# Triangle_VCO.net
KiCad netlist of a schematic drawn in Altium Designer
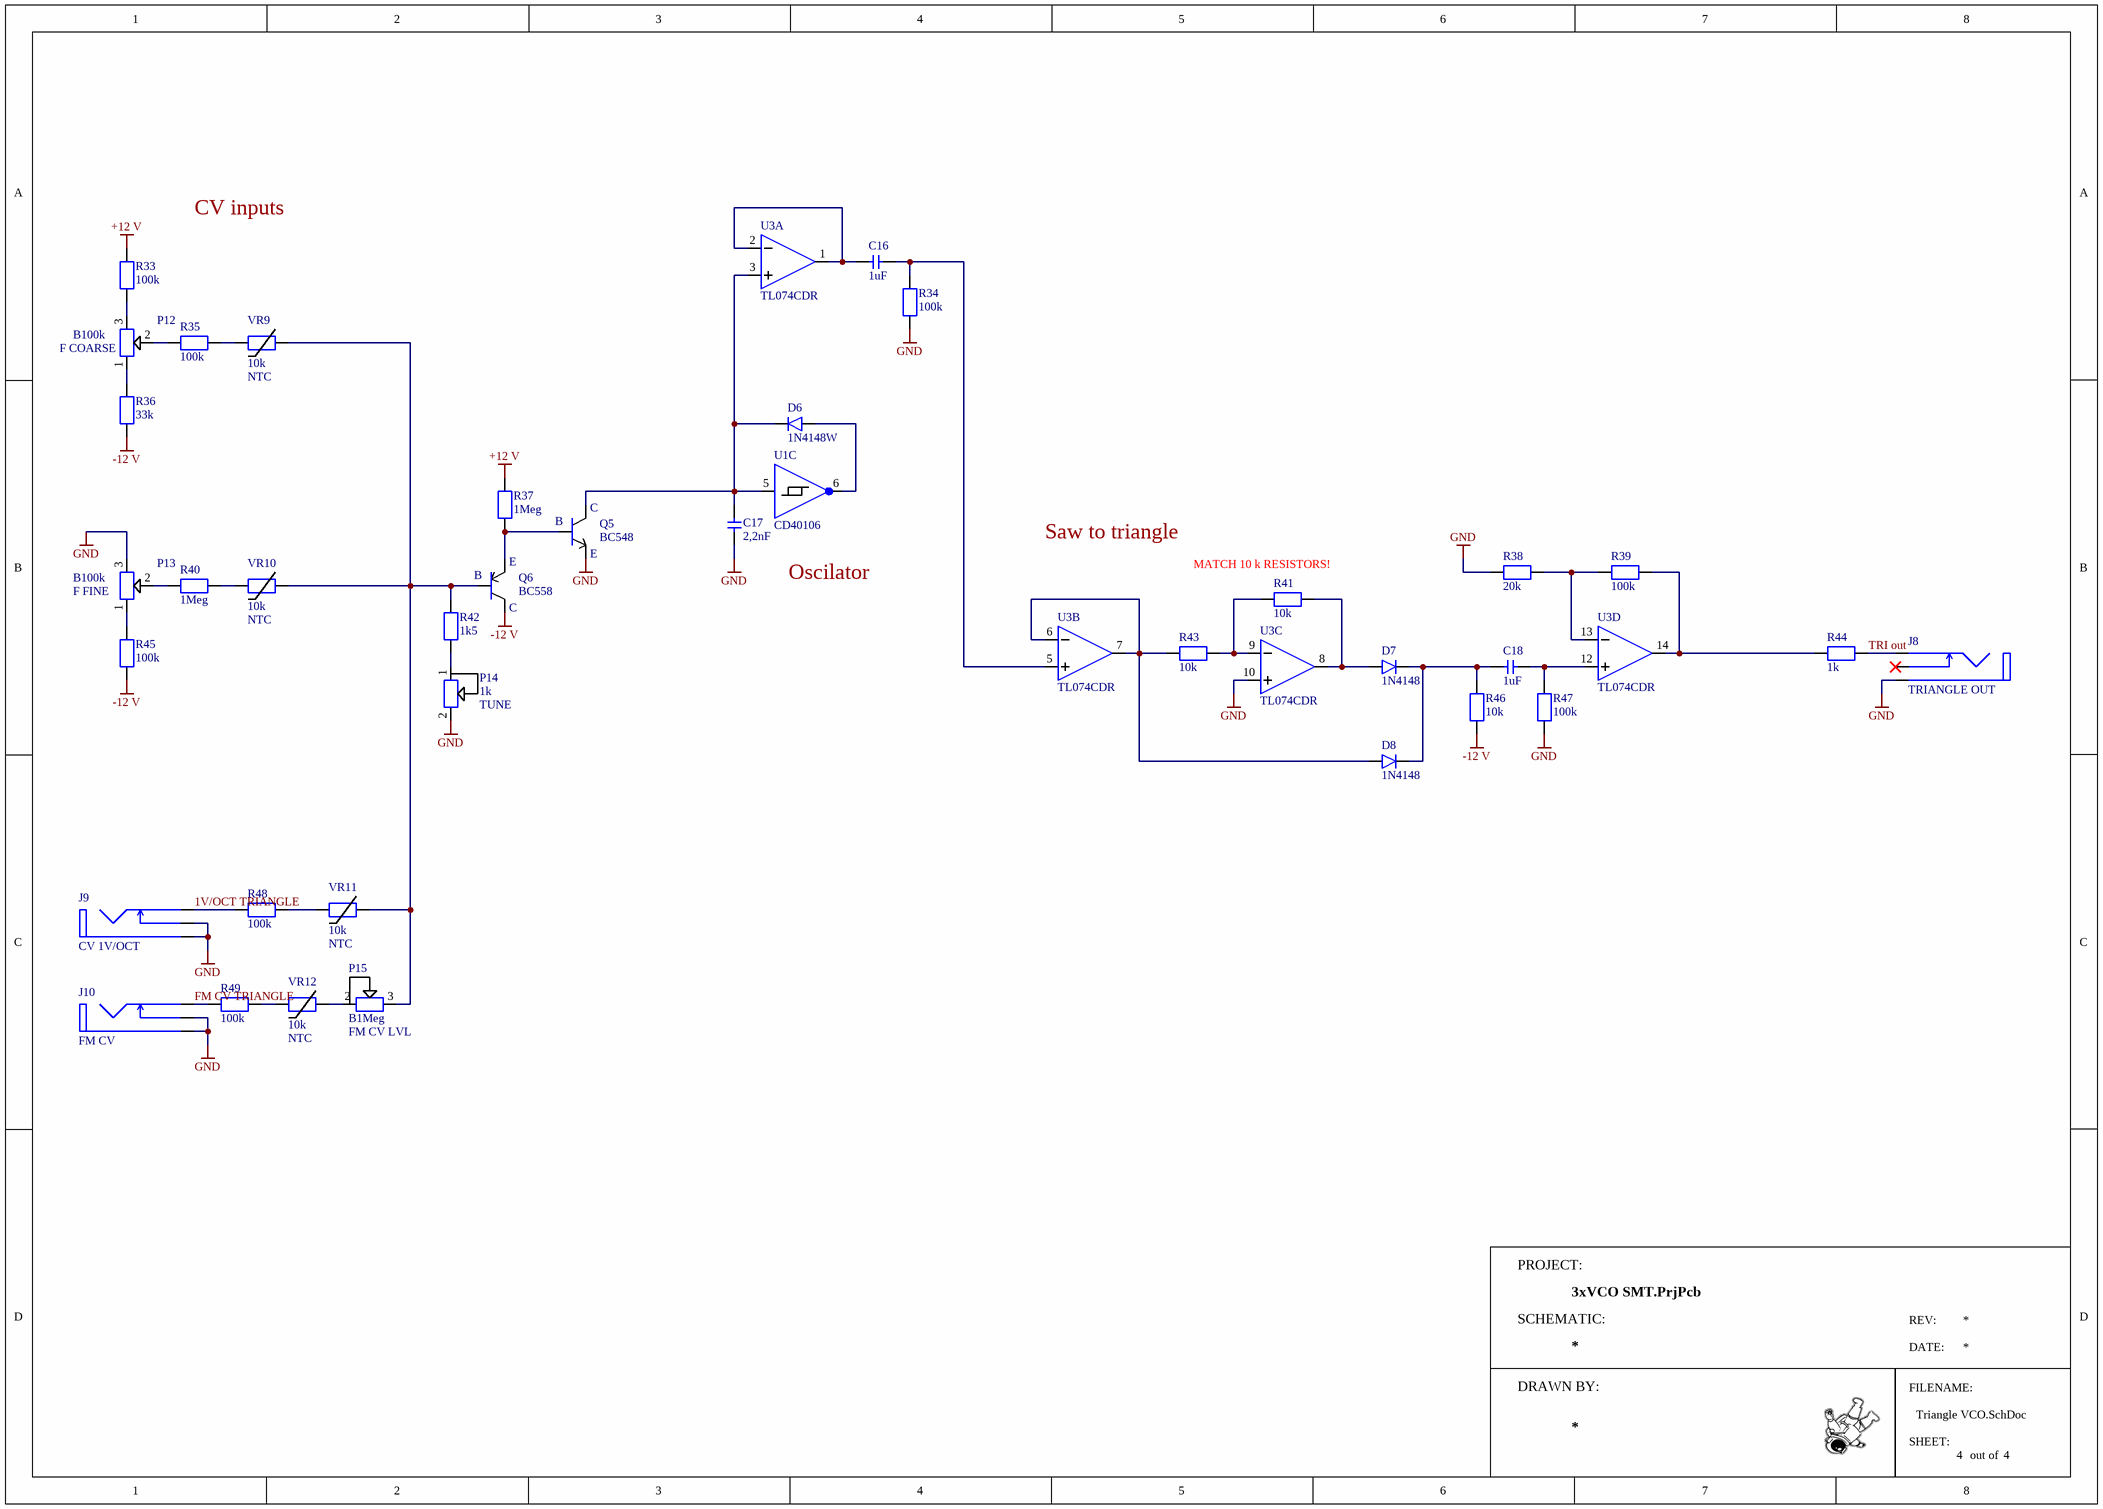
[diagram p0: Triangle VCO.SchDoc]

(export (version "E")
  (design (tool "Eeschema 10.0.6"))
  (components
    (comp (ref "C16")
      (value "1uF")
      (footprint "Cap SMD 0805")
      (description "SMD Capacitor Non-Polarised 0805 Package")
      (fields (field (name "Comment") "CAP"))
      (libsource (lib "Generic components") (part "Capacitor SMD 0805"))
    )
    (comp (ref "C17")
      (value "2,2nF")
      (footprint "Cap SMD 0805")
      (description "SMD Capacitor Non-Polarised 0805 Package")
      (fields (field (name "Comment") "CAP"))
      (libsource (lib "Generic components") (part "Capacitor SMD 0805"))
    )
    (comp (ref "C18")
      (value "1uF")
      (footprint "Cap SMD 0805")
      (description "SMD Capacitor Non-Polarised 0805 Package")
      (fields (field (name "Comment") "CAP"))
      (libsource (lib "Generic components") (part "Capacitor SMD 0805"))
    )
    (comp (ref "D6")
      (value "DIODE")
      (footprint "SOD-123")
      (description "Generic SMD Diode SOD123 Package")
      (fields (field (name "MODEL") "1N4148W"))
      (libsource (lib "Diodes") (part "Diode SMD SOD123"))
    )
    (comp (ref "D7")
      (value "DIODE")
      (footprint "Diode THT 10 mm")
      (description "Generic THT Axial Diode 10 mm Pitch")
      (fields (field (name "MODEL") "1N4148"))
      (libsource (lib "Diodes") (part "Diode THT"))
    )
    (comp (ref "D8")
      (value "DIODE")
      (footprint "Diode THT 10 mm")
      (description "Generic THT Axial Diode 10 mm Pitch")
      (fields (field (name "MODEL") "1N4148"))
      (libsource (lib "Diodes") (part "Diode THT"))
    )
    (comp (ref "J8")
      (value "JACK Mono")
      (footprint "PJ301M")
      (description "PJ301M Eurorack 3,5 mm Patch Socket PCB Mount")
      (fields (field (name "LABEL") "TRIANGLE OUT"))
      (libsource (lib "Connectors") (part "PJ301M"))
    )
    (comp (ref "J9")
      (value "JACK Mono")
      (footprint "PJ301M")
      (description "PJ301M Eurorack 3,5 mm Patch Socket PCB Mount")
      (fields (field (name "LABEL") "CV 1V/OCT"))
      (libsource (lib "Connectors") (part "PJ301M"))
    )
    (comp (ref "J10")
      (value "JACK Mono")
      (footprint "PJ301M")
      (description "PJ301M Eurorack 3,5 mm Patch Socket PCB Mount")
      (fields (field (name "LABEL") "FM CV"))
      (libsource (lib "Connectors") (part "PJ301M"))
    )
    (comp (ref "P12")
      (value "B100k")
      (footprint "9 mm PCB Potentiometer")
      (description "PCB Mount 9mm Mono Potentiometer THT")
      (fields (field (name "PARAMETER") "F COARSE") (field (name "Comment") "Mono Pot"))
      (libsource (lib "Potentiometers") (part "Potentiometer 9 mm"))
    )
    (comp (ref "P13")
      (value "B100k")
      (footprint "9 mm PCB Potentiometer")
      (description "PCB Mount 9mm Mono Potentiometer THT")
      (fields (field (name "PARAMETER") "F FINE") (field (name "Comment") "Mono Pot"))
      (libsource (lib "Potentiometers") (part "Potentiometer 9 mm"))
    )
    (comp (ref "P14")
      (value "1k")
      (footprint "Multiturn Potentiometer inline")
      (description "PCB Mount Multiturn Trimmer Potentiometer Top Adjustable as Variable Resistor Clockwise Increase")
      (fields (field (name "PARAMETER") "TUNE") (field (name "Comment") "VR"))
      (libsource (lib "Potentiometers") (part "VR A Multiturn THT"))
    )
    (comp (ref "P15")
      (value "B1Meg")
      (footprint "9 mm PCB Potentiometer")
      (description "PCB Mount 9mm Mono Potentiometer THT as Variable Resistor Clockwise Decrease")
      (fields (field (name "PARAMETER") "FM CV LVL") (field (name "Comment") "VR"))
      (libsource (lib "Potentiometers") (part "VR B 9 mm"))
    )
    (comp (ref "Q5")
      (value "BC548")
      (footprint "TO-92 wide")
      (description "BC548 NPN Transistor THT TO-92 Package")
      (libsource (lib "Transistors") (part "BC548"))
    )
    (comp (ref "Q6")
      (value "BC558")
      (footprint "TO-92 wide")
      (description "BC558 PNP Transistor THT TO-92 Package")
      (libsource (lib "Transistors") (part "BC558"))
    )
    (comp (ref "R33")
      (value "100k")
      (footprint "Resistor SMD 0805")
      (description "SMD Resistor 0805 package")
      (fields (field (name "Comment") "RES"))
      (libsource (lib "Generic components") (part "Resistor SMD 0805"))
    )
    (comp (ref "R34")
      (value "100k")
      (footprint "Resistor SMD 0805")
      (description "SMD Resistor 0805 package")
      (fields (field (name "Comment") "RES"))
      (libsource (lib "Generic components") (part "Resistor SMD 0805"))
    )
    (comp (ref "R35")
      (value "100k")
      (footprint "Resistor SMD 0805")
      (description "SMD Resistor 0805 package")
      (fields (field (name "Comment") "RES"))
      (libsource (lib "Generic components") (part "Resistor SMD 0805"))
    )
    (comp (ref "R36")
      (value "33k")
      (footprint "Resistor SMD 0805")
      (description "SMD Resistor 0805 package")
      (fields (field (name "Comment") "RES"))
      (libsource (lib "Generic components") (part "Resistor SMD 0805"))
    )
    (comp (ref "R37")
      (value "1Meg")
      (footprint "Resistor SMD 0805")
      (description "SMD Resistor 0805 package")
      (fields (field (name "Comment") "RES"))
      (libsource (lib "Generic components") (part "Resistor SMD 0805"))
    )
    (comp (ref "R38")
      (value "20k")
      (footprint "Resistor SMD 0805")
      (description "SMD Resistor 0805 package")
      (fields (field (name "Comment") "RES"))
      (libsource (lib "Generic components") (part "Resistor SMD 0805"))
    )
    (comp (ref "R39")
      (value "100k")
      (footprint "Resistor SMD 0805")
      (description "SMD Resistor 0805 package")
      (fields (field (name "Comment") "RES"))
      (libsource (lib "Generic components") (part "Resistor SMD 0805"))
    )
    (comp (ref "R40")
      (value "1Meg")
      (footprint "Resistor SMD 0805")
      (description "SMD Resistor 0805 package")
      (fields (field (name "Comment") "RES"))
      (libsource (lib "Generic components") (part "Resistor SMD 0805"))
    )
    (comp (ref "R41")
      (value "10k")
      (footprint "Resistor THT vertical")
      (description "THT Axial Resistor 10mm Pitch")
      (fields (field (name "Comment") "RES"))
      (libsource (lib "Generic components") (part "Resistor THT"))
    )
    (comp (ref "R42")
      (value "1k5")
      (footprint "Resistor SMD 0805")
      (description "SMD Resistor 0805 package")
      (fields (field (name "Comment") "RES"))
      (libsource (lib "Generic components") (part "Resistor SMD 0805"))
    )
    (comp (ref "R43")
      (value "10k")
      (footprint "Resistor THT vertical")
      (description "THT Axial Resistor 10mm Pitch")
      (fields (field (name "Comment") "RES"))
      (libsource (lib "Generic components") (part "Resistor THT"))
    )
    (comp (ref "R44")
      (value "1k")
      (footprint "Resistor SMD 0805")
      (description "SMD Resistor 0805 package")
      (fields (field (name "Comment") "RES"))
      (libsource (lib "Generic components") (part "Resistor SMD 0805"))
    )
    (comp (ref "R45")
      (value "100k")
      (footprint "Resistor SMD 0805")
      (description "SMD Resistor 0805 package")
      (fields (field (name "Comment") "RES"))
      (libsource (lib "Generic components") (part "Resistor SMD 0805"))
    )
    (comp (ref "R46")
      (value "10k")
      (footprint "Resistor SMD 0805")
      (description "SMD Resistor 0805 package")
      (fields (field (name "Comment") "RES"))
      (libsource (lib "Generic components") (part "Resistor SMD 0805"))
    )
    (comp (ref "R47")
      (value "100k")
      (footprint "Resistor SMD 0805")
      (description "SMD Resistor 0805 package")
      (fields (field (name "Comment") "RES"))
      (libsource (lib "Generic components") (part "Resistor SMD 0805"))
    )
    (comp (ref "R48")
      (value "100k")
      (footprint "Resistor SMD 0805")
      (description "SMD Resistor 0805 package")
      (fields (field (name "Comment") "RES"))
      (libsource (lib "Generic components") (part "Resistor SMD 0805"))
    )
    (comp (ref "R49")
      (value "100k")
      (footprint "Resistor SMD 0805")
      (description "SMD Resistor 0805 package")
      (fields (field (name "Comment") "RES"))
      (libsource (lib "Generic components") (part "Resistor SMD 0805"))
    )
    (comp (ref "U1")
      (value "CD40106")
      (footprint "DIP-14 socket")
      (description "CD40106 Hex Schmitt Trigger Inverter DIP-14 Package")
      (libsource (lib "ICs") (part "CD40106 DIP-14"))
    )
    (comp (ref "U3")
      (value "TL074CDR")
      (footprint "SOIC14")
      (description "TL074CDR Quad Op-Amp SOIC14 Package")
      (libsource (lib "OpAmps") (part "TL074CDR SOIC14"))
    )
    (comp (ref "VR9")
      (value "NTC")
      (footprint "Thermistor SMD 0805")
      (description "SMD NTC Thermistor 0805 package")
      (fields (field (name "ALTIUM_VALUE") "10k"))
      (libsource (lib "Generic components") (part "Thermistor NTC SMD 0805"))
    )
    (comp (ref "VR10")
      (value "NTC")
      (footprint "Thermistor SMD 0805")
      (description "SMD NTC Thermistor 0805 package")
      (fields (field (name "ALTIUM_VALUE") "10k"))
      (libsource (lib "Generic components") (part "Thermistor NTC SMD 0805"))
    )
    (comp (ref "VR11")
      (value "NTC")
      (footprint "Thermistor SMD 0805")
      (description "SMD NTC Thermistor 0805 package")
      (fields (field (name "ALTIUM_VALUE") "10k"))
      (libsource (lib "Generic components") (part "Thermistor NTC SMD 0805"))
    )
    (comp (ref "VR12")
      (value "NTC")
      (footprint "Thermistor SMD 0805")
      (description "SMD NTC Thermistor 0805 package")
      (fields (field (name "ALTIUM_VALUE") "10k"))
      (libsource (lib "Generic components") (part "Thermistor NTC SMD 0805"))
    )
  )
  (nets
    (net (code "1") (name "+12 V") (class "Default")
      (node (ref "R33") (pin "2") (pintype "passive"))
      (node (ref "R37") (pin "1") (pintype "passive"))
    )
    (net (code "2") (name "-12 V") (class "Default")
      (node (ref "Q6") (pin "1") (pintype "passive"))
      (node (ref "R36") (pin "1") (pintype "passive"))
      (node (ref "R45") (pin "1") (pintype "passive"))
      (node (ref "R46") (pin "2") (pintype "passive"))
    )
    (net (code "3") (name "/1V{slash}OCT TRIANGLE") (class "Default")
      (node (ref "J9") (pin "3") (pintype "passive"))
      (node (ref "R48") (pin "2") (pintype "passive"))
    )
    (net (code "4") (name "/FM CV TRIANGLE") (class "Default")
      (node (ref "J10") (pin "3") (pintype "passive"))
      (node (ref "R49") (pin "2") (pintype "passive"))
    )
    (net (code "5") (name "/TRI out") (class "Default")
      (node (ref "J8") (pin "3") (pintype "passive"))
      (node (ref "R44") (pin "2") (pintype "passive"))
    )
    (net (code "6") (name "GND") (class "Default")
      (node (ref "C17") (pin "1") (pintype "passive"))
      (node (ref "J10") (pin "1") (pintype "passive"))
      (node (ref "J10") (pin "2") (pintype "passive"))
      (node (ref "J8") (pin "1") (pintype "passive"))
      (node (ref "J9") (pin "1") (pintype "passive"))
      (node (ref "J9") (pin "2") (pintype "passive"))
      (node (ref "P13") (pin "3") (pintype "passive"))
      (node (ref "P14") (pin "2") (pintype "passive"))
      (node (ref "Q5") (pin "3") (pintype "passive"))
      (node (ref "R34") (pin "2") (pintype "passive"))
      (node (ref "R38") (pin "1") (pintype "passive"))
      (node (ref "R47") (pin "2") (pintype "passive"))
      (node (ref "U3") (pin "10") (pintype "passive"))
    )
    (net (code "7") (name "Net-(C16-Pad1)") (class "Default")
      (node (ref "C16") (pin "1") (pintype "passive"))
      (node (ref "R34") (pin "1") (pintype "passive"))
      (node (ref "U3") (pin "5") (pintype "passive"))
    )
    (net (code "8") (name "Net-(C16-Pad2)") (class "Default")
      (node (ref "C16") (pin "2") (pintype "passive"))
      (node (ref "U3") (pin "1") (pintype "passive"))
      (node (ref "U3") (pin "2") (pintype "passive"))
    )
    (net (code "9") (name "Net-(C17-Pad2)") (class "Default")
      (node (ref "C17") (pin "2") (pintype "passive"))
      (node (ref "D6") (pin "2") (pintype "passive"))
      (node (ref "Q5") (pin "1") (pintype "passive"))
      (node (ref "U1") (pin "5") (pintype "passive"))
      (node (ref "U3") (pin "3") (pintype "passive"))
    )
    (net (code "10") (name "Net-(C18-Pad1)") (class "Default")
      (node (ref "C18") (pin "1") (pintype "passive"))
      (node (ref "R47") (pin "1") (pintype "passive"))
      (node (ref "U3") (pin "12") (pintype "passive"))
    )
    (net (code "11") (name "Net-(C18-Pad2)") (class "Default")
      (node (ref "C18") (pin "2") (pintype "passive"))
      (node (ref "D7") (pin "2") (pintype "passive"))
      (node (ref "D8") (pin "2") (pintype "passive"))
      (node (ref "R46") (pin "1") (pintype "passive"))
    )
    (net (code "12") (name "Net-(D6-Pad1)") (class "Default")
      (node (ref "D6") (pin "1") (pintype "passive"))
      (node (ref "U1") (pin "6") (pintype "passive"))
    )
    (net (code "13") (name "Net-(D7-Pad1)") (class "Default")
      (node (ref "D7") (pin "1") (pintype "passive"))
      (node (ref "R41") (pin "2") (pintype "passive"))
      (node (ref "U3") (pin "8") (pintype "passive"))
    )
    (net (code "14") (name "Net-(D8-Pad1)") (class "Default")
      (node (ref "D8") (pin "1") (pintype "passive"))
      (node (ref "R43") (pin "1") (pintype "passive"))
      (node (ref "U3") (pin "6") (pintype "passive"))
      (node (ref "U3") (pin "7") (pintype "passive"))
    )
    (net (code "15") (name "Net-(P12-Pad1)") (class "Default")
      (node (ref "P12") (pin "1") (pintype "passive"))
      (node (ref "R36") (pin "2") (pintype "passive"))
    )
    (net (code "16") (name "Net-(P12-Pad2)") (class "Default")
      (node (ref "P12") (pin "2") (pintype "passive"))
      (node (ref "R35") (pin "2") (pintype "passive"))
    )
    (net (code "17") (name "Net-(P12-Pad3)") (class "Default")
      (node (ref "P12") (pin "3") (pintype "passive"))
      (node (ref "R33") (pin "1") (pintype "passive"))
    )
    (net (code "18") (name "Net-(P13-Pad1)") (class "Default")
      (node (ref "P13") (pin "1") (pintype "passive"))
      (node (ref "R45") (pin "2") (pintype "passive"))
    )
    (net (code "19") (name "Net-(P13-Pad2)") (class "Default")
      (node (ref "P13") (pin "2") (pintype "passive"))
      (node (ref "R40") (pin "2") (pintype "passive"))
    )
    (net (code "20") (name "Net-(P14-Pad1)") (class "Default")
      (node (ref "P14") (pin "1") (pintype "passive"))
      (node (ref "R42") (pin "2") (pintype "passive"))
    )
    (net (code "21") (name "Net-(P15-Pad2)") (class "Default")
      (node (ref "P15") (pin "2") (pintype "passive"))
      (node (ref "VR12") (pin "2") (pintype "passive"))
    )
    (net (code "22") (name "Net-(P15-Pad3)") (class "Default")
      (node (ref "P15") (pin "3") (pintype "passive"))
      (node (ref "Q6") (pin "2") (pintype "passive"))
      (node (ref "R42") (pin "1") (pintype "passive"))
      (node (ref "VR10") (pin "2") (pintype "passive"))
      (node (ref "VR11") (pin "2") (pintype "passive"))
      (node (ref "VR9") (pin "2") (pintype "passive"))
    )
    (net (code "23") (name "Net-(Q5-Pad2)") (class "Default")
      (node (ref "Q5") (pin "2") (pintype "passive"))
      (node (ref "Q6") (pin "3") (pintype "passive"))
      (node (ref "R37") (pin "2") (pintype "passive"))
    )
    (net (code "24") (name "Net-(R35-Pad1)") (class "Default")
      (node (ref "R35") (pin "1") (pintype "passive"))
      (node (ref "VR9") (pin "1") (pintype "passive"))
    )
    (net (code "25") (name "Net-(R38-Pad2)") (class "Default")
      (node (ref "R38") (pin "2") (pintype "passive"))
      (node (ref "R39") (pin "1") (pintype "passive"))
      (node (ref "U3") (pin "13") (pintype "passive"))
    )
    (net (code "26") (name "Net-(R39-Pad2)") (class "Default")
      (node (ref "R39") (pin "2") (pintype "passive"))
      (node (ref "R44") (pin "1") (pintype "passive"))
      (node (ref "U3") (pin "14") (pintype "passive"))
    )
    (net (code "27") (name "Net-(R40-Pad1)") (class "Default")
      (node (ref "R40") (pin "1") (pintype "passive"))
      (node (ref "VR10") (pin "1") (pintype "passive"))
    )
    (net (code "28") (name "Net-(R41-Pad1)") (class "Default")
      (node (ref "R41") (pin "1") (pintype "passive"))
      (node (ref "R43") (pin "2") (pintype "passive"))
      (node (ref "U3") (pin "9") (pintype "passive"))
    )
    (net (code "29") (name "Net-(R48-Pad1)") (class "Default")
      (node (ref "R48") (pin "1") (pintype "passive"))
      (node (ref "VR11") (pin "1") (pintype "passive"))
    )
    (net (code "30") (name "Net-(R49-Pad1)") (class "Default")
      (node (ref "R49") (pin "1") (pintype "passive"))
      (node (ref "VR12") (pin "1") (pintype "passive"))
    )
    (net (code "31") (name "unconnected-(J8-Pad2)") (class "Default")
      (node (ref "J8") (pin "2") (pintype "passive+no_connect"))
    )
  )
)
